# Electromagnet.net
KiCad netlist of a schematic drawn in Altium Designer
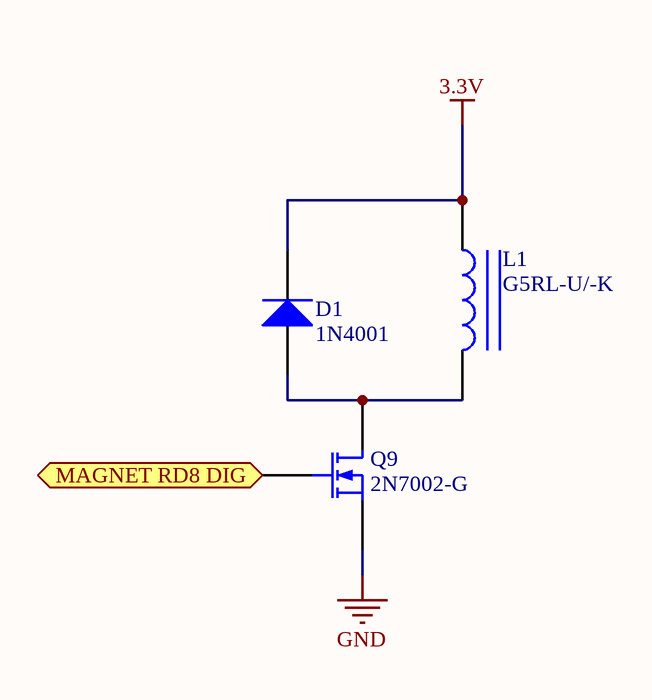
[diagram p0: Electromagnet.SchDoc]

(export (version "E")
  (design (tool "Eeschema 10.0.6"))
  (components
    (comp (ref "D1")
      (value "1N4001")
      (footprint "Diode")
      (description "Default Diode")
      (fields (field (name "PUBLISHER") "Altium Limited"))
      (libsource (lib "Miscellaneous Devices") (part "Diode"))
    )
    (comp (ref "L1")
      (value "G5RL-U/-K")
      (footprint "Electromagnet")
      (description "Magnetic-Core Inductor")
      (fields (field (name "PUBLISHER") "Altium Limited"))
      (libsource (lib "Miscellaneous Devices") (part "Inductor Iron"))
    )
    (comp (ref "Q9")
      (value "2N7002-G")
      (footprint "Mosfet")
      (description "N-Channel MOSFET")
      (fields (field (name "PUBLISHER") "Altium Limited"))
      (libsource (lib "Miscellaneous Devices") (part "MOSFET-N"))
    )
  )
  (nets
    (net (code "1") (name "/MAGNET RD8 DIG") (class "Default")
      (node (ref "Q9") (pin "1") (pinfunction "G_1") (pintype "passive"))
    )
    (net (code "2") (name "3.3V") (class "Default")
      (node (ref "D1") (pin "2") (pinfunction "K_2") (pintype "passive"))
      (node (ref "L1") (pin "1") (pinfunction "1_1") (pintype "passive"))
    )
    (net (code "3") (name "GND") (class "Default")
      (node (ref "Q9") (pin "2") (pinfunction "S_2") (pintype "passive"))
    )
    (net (code "4") (name "Net-(D1-A)") (class "Default")
      (node (ref "D1") (pin "1") (pinfunction "A_1") (pintype "passive"))
      (node (ref "L1") (pin "2") (pinfunction "2_2") (pintype "passive"))
      (node (ref "Q9") (pin "3") (pinfunction "D_3") (pintype "passive"))
    )
  )
)
